# Kapasitor_Kart_v1_0.net
KiCad netlist of a schematic drawn in Altium Designer
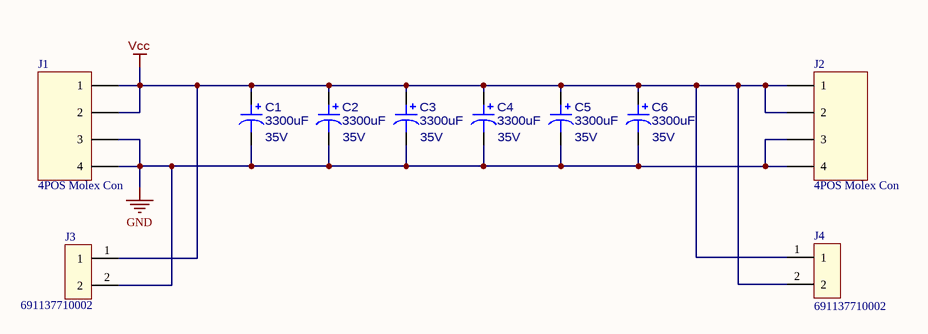
[diagram p0: Kapasitor Kart v1.0.SchDoc]

(export (version "E")
  (design (tool "Eeschema 10.0.6"))
  (components
    (comp (ref "C1")
      (value "3300uF")
      (footprint "TH/C/7.50mm")
      (description "PKR3-035V332MJ250")
      (fields (field (name "VOLT") "35V"))
      (libsource (lib "Kapasitor Kart v1.0") (part "AlumCap"))
    )
    (comp (ref "C2")
      (value "3300uF")
      (footprint "TH/C/7.50mm")
      (description "PKR3-035V332MJ250")
      (fields (field (name "VOLT") "35V"))
      (libsource (lib "Kapasitor Kart v1.0") (part "AlumCap"))
    )
    (comp (ref "C3")
      (value "3300uF")
      (footprint "TH/C/7.50mm")
      (description "PKR3-035V332MJ250")
      (fields (field (name "VOLT") "35V"))
      (libsource (lib "Kapasitor Kart v1.0") (part "AlumCap"))
    )
    (comp (ref "C4")
      (value "3300uF")
      (footprint "TH/C/7.50mm")
      (description "PKR3-035V332MJ250")
      (fields (field (name "VOLT") "35V"))
      (libsource (lib "Kapasitor Kart v1.0") (part "AlumCap"))
    )
    (comp (ref "C5")
      (value "3300uF")
      (footprint "TH/C/7.50mm")
      (description "PKR3-035V332MJ250")
      (fields (field (name "VOLT") "35V"))
      (libsource (lib "Kapasitor Kart v1.0") (part "AlumCap"))
    )
    (comp (ref "C6")
      (value "3300uF")
      (footprint "TH/C/7.50mm")
      (description "PKR3-035V332MJ250")
      (fields (field (name "VOLT") "35V"))
      (libsource (lib "Kapasitor Kart v1.0") (part "AlumCap"))
    )
    (comp (ref "J1")
      (value "4POS Molex Con")
      (footprint "87438-0443")
      (description "4 CKT 1.5mm HDR. Rt.-Angle SMT")
      (libsource (lib "") (part "87438-0443_1"))
    )
    (comp (ref "J2")
      (value "4POS Molex Con")
      (footprint "87438-0443")
      (description "4 CKT 1.5mm HDR. Rt.-Angle SMT")
      (libsource (lib "Kapasitor Kart v1.0") (part "87438-0443"))
    )
    (comp (ref "J3")
      (value "691137710002")
      (footprint "691137710002")
      (description "2 Position Wire to Board Terminal Block Horizontal with Board 0.197\" (5.00mm) Through Hole")
      (libsource (lib "Kapasitor Kart v1.0") (part "691137710002"))
    )
    (comp (ref "J4")
      (value "691137710002")
      (footprint "691137710002")
      (description "2 Position Wire to Board Terminal Block Horizontal with Board 0.197\" (5.00mm) Through Hole")
      (libsource (lib "") (part "691137710002_1"))
    )
  )
  (nets
    (net (code "1") (name "GND") (class "Default")
      (node (ref "C1") (pin "2") (pinfunction "2_2") (pintype "passive"))
      (node (ref "C2") (pin "2") (pinfunction "2_2") (pintype "passive"))
      (node (ref "C3") (pin "2") (pinfunction "2_2") (pintype "passive"))
      (node (ref "C4") (pin "2") (pinfunction "2_2") (pintype "passive"))
      (node (ref "C5") (pin "2") (pinfunction "2_2") (pintype "passive"))
      (node (ref "C6") (pin "2") (pinfunction "2_2") (pintype "passive"))
      (node (ref "J1") (pin "3") (pinfunction "3_3") (pintype "passive"))
      (node (ref "J1") (pin "4") (pinfunction "4_4") (pintype "passive"))
      (node (ref "J2") (pin "3") (pinfunction "3_3") (pintype "passive"))
      (node (ref "J2") (pin "4") (pinfunction "4_4") (pintype "passive"))
      (node (ref "J3") (pin "2") (pinfunction "2_2") (pintype "passive"))
    )
    (net (code "2") (name "Vcc") (class "Default")
      (node (ref "C1") (pin "1") (pinfunction "1_1") (pintype "passive"))
      (node (ref "C2") (pin "1") (pinfunction "1_1") (pintype "passive"))
      (node (ref "C3") (pin "1") (pinfunction "1_1") (pintype "passive"))
      (node (ref "C4") (pin "1") (pinfunction "1_1") (pintype "passive"))
      (node (ref "C5") (pin "1") (pinfunction "1_1") (pintype "passive"))
      (node (ref "C6") (pin "1") (pinfunction "1_1") (pintype "passive"))
      (node (ref "J1") (pin "1") (pinfunction "1_1") (pintype "passive"))
      (node (ref "J1") (pin "2") (pinfunction "2_2") (pintype "passive"))
      (node (ref "J2") (pin "1") (pinfunction "1_1") (pintype "passive"))
      (node (ref "J2") (pin "2") (pinfunction "2_2") (pintype "passive"))
      (node (ref "J3") (pin "1") (pinfunction "1_1") (pintype "passive"))
      (node (ref "J4") (pin "1") (pinfunction "1_1") (pintype "passive"))
      (node (ref "J4") (pin "2") (pinfunction "2_2") (pintype "passive"))
    )
  )
)
